# POWER_Management.net
KiCad netlist of a schematic drawn in Altium Designer
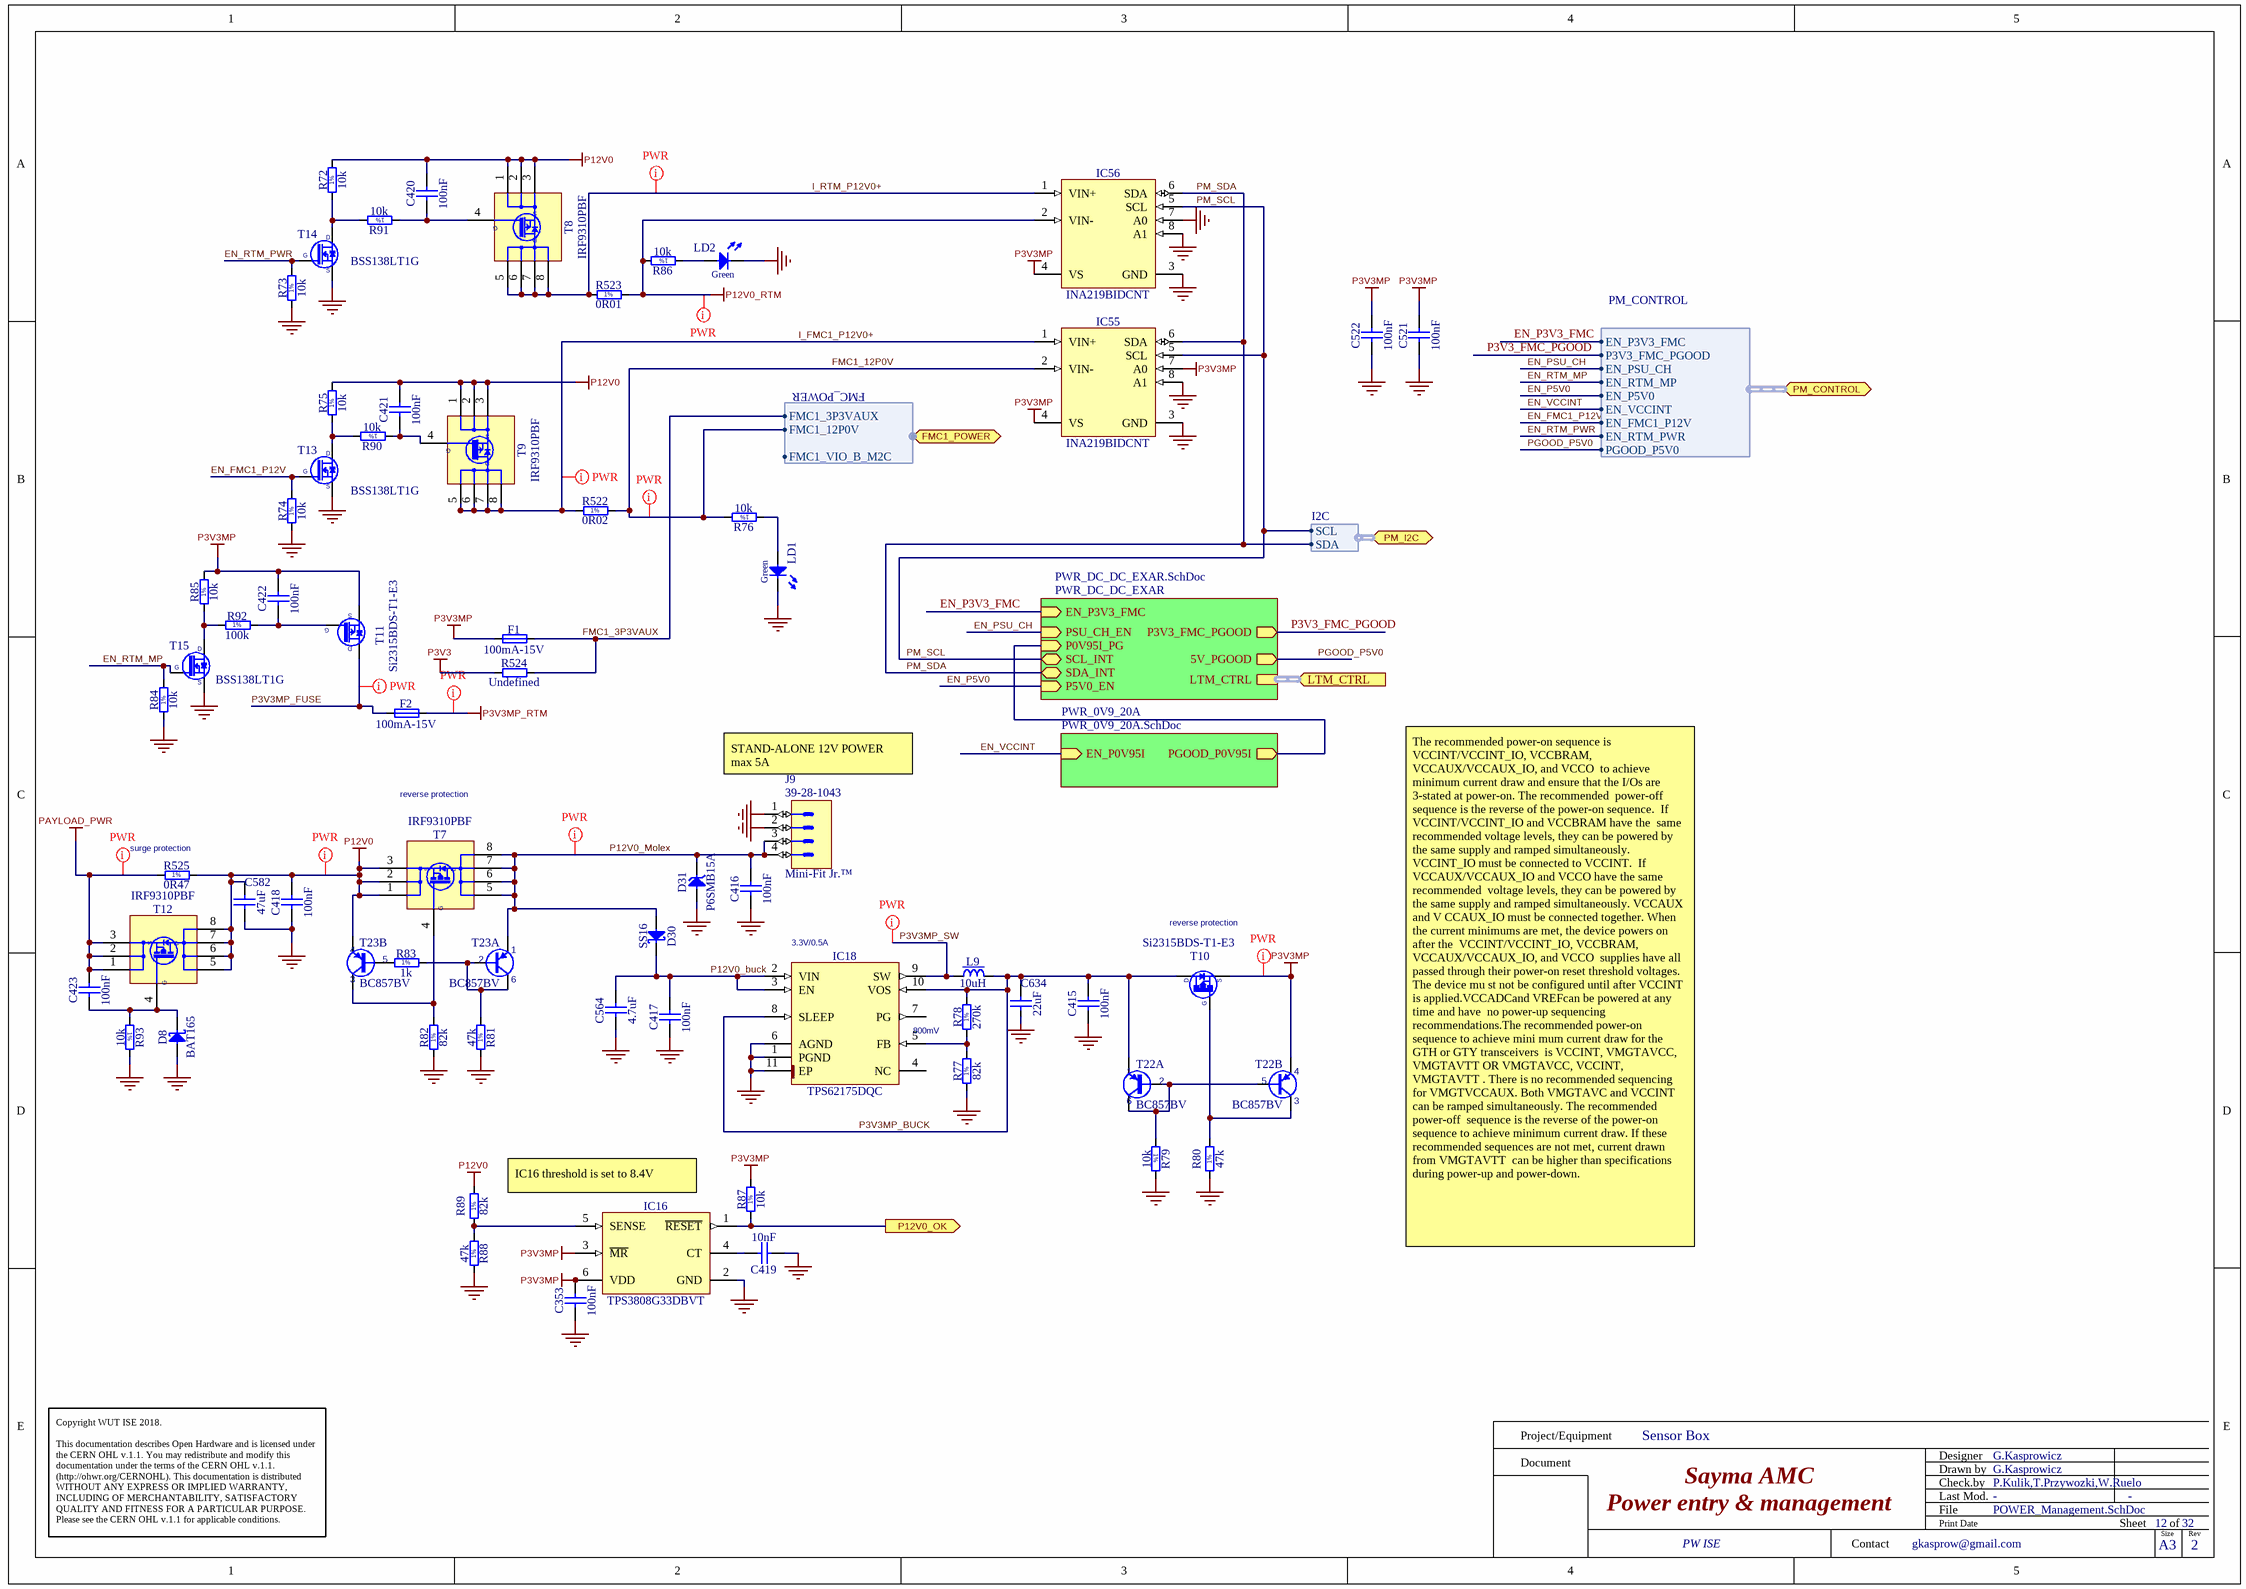
[diagram p0: POWER_Management.SchDoc]

(export (version "E")
  (design (tool "Eeschema 10.0.6"))
  (components
    (comp (ref "C353")
      (value "100nF")
      (footprint "CAPC1005X55N")
      (description "Non-polarised capacitor")
      (fields
        (field (name "MANUFACTURER PART NUMBER") "CC0402_100NF_16V_10%_X5R")
        (field (name "MANUFACTURER") "GENERIC")
        (field (name "AUTHOR") "CERN DEM JLC")
      )
      (libsource (lib "Capacitors") (part "Capacitor - non polarized"))
    )
    (comp (ref "C415")
      (value "100nF")
      (footprint "CAPC1005X55N")
      (description "Non-polarised capacitor")
      (fields
        (field (name "MANUFACTURER PART NUMBER") "CC0402_100NF_16V_10%_X5R")
        (field (name "MANUFACTURER") "GENERIC")
        (field (name "AUTHOR") "CERN DEM JLC")
      )
      (libsource (lib "Capacitors") (part "Capacitor - non polarized"))
    )
    (comp (ref "C416")
      (value "100nF")
      (footprint "CAPC1005X55N")
      (description "Non-polarised capacitor")
      (fields
        (field (name "MANUFACTURER PART NUMBER") "CC0402_100NF_16V_10%_X5R")
        (field (name "MANUFACTURER") "GENERIC")
        (field (name "AUTHOR") "CERN DEM JLC")
      )
      (libsource (lib "Capacitors") (part "Capacitor - non polarized"))
    )
    (comp (ref "C417")
      (value "100nF")
      (footprint "CAPC1005X55N")
      (description "Non-polarised capacitor")
      (fields
        (field (name "MANUFACTURER PART NUMBER") "CC0402_100NF_16V_10%_X5R")
        (field (name "MANUFACTURER") "GENERIC")
        (field (name "AUTHOR") "CERN DEM JLC")
      )
      (libsource (lib "Capacitors") (part "Capacitor - non polarized"))
    )
    (comp (ref "C418")
      (value "100nF")
      (footprint "CAPC1005X55N")
      (description "Non-polarised capacitor")
      (fields
        (field (name "MANUFACTURER PART NUMBER") "CC0402_100NF_16V_10%_X5R")
        (field (name "MANUFACTURER") "GENERIC")
        (field (name "AUTHOR") "CERN DEM JLC")
      )
      (libsource (lib "Capacitors") (part "Capacitor - non polarized"))
    )
    (comp (ref "C419")
      (value "10nF")
      (footprint "CAPC1005X55N")
      (description "Non-polarised capacitor")
      (fields
        (field (name "MANUFACTURER PART NUMBER") "CC0402_10NF_16V_10%_X7R")
        (field (name "MANUFACTURER") "GENERIC")
        (field (name "AUTHOR") "CERN DEM JLC")
      )
      (libsource (lib "Capacitors") (part "Capacitor - non polarized"))
    )
    (comp (ref "C420")
      (value "100nF")
      (footprint "CAPC1005X55N")
      (description "Non-polarised capacitor")
      (fields
        (field (name "MANUFACTURER PART NUMBER") "CC0402_100NF_16V_10%_X5R")
        (field (name "MANUFACTURER") "GENERIC")
        (field (name "AUTHOR") "CERN DEM JLC")
      )
      (libsource (lib "Capacitors") (part "Capacitor - non polarized"))
    )
    (comp (ref "C421")
      (value "100nF")
      (footprint "CAPC1005X55N")
      (description "Non-polarised capacitor")
      (fields
        (field (name "MANUFACTURER PART NUMBER") "CC0402_100NF_16V_10%_X5R")
        (field (name "MANUFACTURER") "GENERIC")
        (field (name "AUTHOR") "CERN DEM JLC")
      )
      (libsource (lib "Capacitors") (part "Capacitor - non polarized"))
    )
    (comp (ref "C422")
      (value "100nF")
      (footprint "CAPC1005X55N")
      (description "Non-polarised capacitor")
      (fields
        (field (name "MANUFACTURER PART NUMBER") "CC0402_100NF_16V_10%_X5R")
        (field (name "MANUFACTURER") "GENERIC")
        (field (name "AUTHOR") "CERN DEM JLC")
      )
      (libsource (lib "Capacitors") (part "Capacitor - non polarized"))
    )
    (comp (ref "C423")
      (value "100nF")
      (footprint "CAPC1005X55N")
      (description "Non-polarised capacitor")
      (fields
        (field (name "MANUFACTURER PART NUMBER") "CC0402_100NF_16V_10%_X5R")
        (field (name "MANUFACTURER") "GENERIC")
        (field (name "AUTHOR") "CERN DEM JLC")
      )
      (libsource (lib "Capacitors") (part "Capacitor - non polarized"))
    )
    (comp (ref "C521")
      (value "100nF")
      (footprint "CAPC1005X55N")
      (description "Non-polarised capacitor")
      (fields
        (field (name "MANUFACTURER PART NUMBER") "CC0402_100NF_16V_10%_X5R")
        (field (name "MANUFACTURER") "GENERIC")
        (field (name "AUTHOR") "CERN DEM JLC")
      )
      (libsource (lib "Capacitors") (part "Capacitor - non polarized"))
    )
    (comp (ref "C522")
      (value "100nF")
      (footprint "CAPC1005X55N")
      (description "Non-polarised capacitor")
      (fields
        (field (name "MANUFACTURER PART NUMBER") "CC0402_100NF_16V_10%_X5R")
        (field (name "MANUFACTURER") "GENERIC")
        (field (name "AUTHOR") "CERN DEM JLC")
      )
      (libsource (lib "Capacitors") (part "Capacitor - non polarized"))
    )
    (comp (ref "C564")
      (value "4.7uF")
      (footprint "CAPC1709X95N")
      (description "Non-polarised capacitor")
      (fields
        (field (name "MANUFACTURER PART NUMBER") "CC0603_4.7UF_16V_10%_X5R")
        (field (name "MANUFACTURER") "GENERIC")
        (field (name "AUTHOR") "CERN DEM JLC")
      )
      (libsource (lib "Capacitors") (part "Capacitor - non polarized"))
    )
    (comp (ref "C582")
      (value "47uF")
      (footprint "CAPC3216X180N")
      (description "Non-polarised capacitor")
      (fields
        (field (name "MANUFACTURER PART NUMBER") "CC1206_47UF_25V_20%_X5R")
        (field (name "MANUFACTURER") "GENERIC")
        (field (name "AUTHOR") "CERN DEM JLC")
      )
      (libsource (lib "Capacitors") (part "Capacitor - non polarized"))
    )
    (comp (ref "C634")
      (value "22uF")
      (footprint "CAPC2012X135N")
      (description "Non-polarised capacitor")
      (fields
        (field (name "MANUFACTURER PART NUMBER") "CC0805_22UF_16V_10%_X5R")
        (field (name "MANUFACTURER") "GENERIC")
        (field (name "AUTHOR") "CERN DEM JLC")
      )
      (libsource (lib "Capacitors") (part "Capacitor - non polarized"))
    )
    (comp (ref "D8")
      (value "BAT165")
      (footprint "SOD2512X110N")
      (description "Schottky Diode")
      (fields
        (field (name "MANUFACTURER") "INFINEON")
        (field (name "VOLTAGE") "40V")
        (field (name "AUTHOR") "CERN DEM JLC")
      )
      (libsource (lib "ICs And Semiconductors") (part "Diode Schottky"))
    )
    (comp (ref "D30")
      (value "SS16")
      (footprint "DIOM5127X229N")
      (description "Schottky Diode")
      (fields
        (field (name "MANUFACTURER") "VISHAY GENERAL SEMICONDUCTOR")
        (field (name "VOLTAGE") "60V")
        (field (name "AUTHOR") "CERN DEM JLC")
      )
      (libsource (lib "ICs And Semiconductors") (part "Diode Schottky"))
    )
    (comp (ref "D31")
      (value "P6SMB15A")
      (footprint "DIOM5436X261N")
      (description "Transient Voltage Suppressor Diode (Uni-Directional)")
      (fields
        (field (name "MANUFACTURER") "LITTELFUSE")
        (field (name "VOLTAGE") "15V")
        (field (name "AUTHOR") "CERN DEM JLC")
      )
      (libsource (lib "ICs And Semiconductors") (part "Diode TVS Uni-Directional"))
    )
    (comp (ref "F1")
      (value "100mA-15V")
      (footprint "FUSR_LITTELFUSE_0805L010")
      (description "Fuse")
      (fields
        (field (name "MANUFACTURER PART NUMBER") "0805L010YR")
        (field (name "MANUFACTURER") "LITTELFUSE")
        (field (name "AUTHOR") "CERN DEM JLC")
      )
      (libsource (lib "Eletro-mechanical") (part "Fuse"))
    )
    (comp (ref "F2")
      (value "100mA-15V")
      (footprint "FUSR_LITTELFUSE_0805L010")
      (description "Fuse")
      (fields
        (field (name "MANUFACTURER PART NUMBER") "0805L010YR")
        (field (name "MANUFACTURER") "LITTELFUSE")
        (field (name "AUTHOR") "CERN DEM JLC")
      )
      (libsource (lib "Eletro-mechanical") (part "Fuse"))
    )
    (comp (ref "IC16")
      (value "TPS3808G33DBVT")
      (footprint "SOT95P280X145-6N")
      (description "Low Quiescent Current, Programmable-Delay Supervisory Circuit")
      (fields (field (name "MANUFACTURER") "TEXAS INSTRUMENTS") (field (name "AUTHOR") "CERN DEM JLC"))
      (libsource (lib "ICs And Semiconductors") (part "TPS3808xxxDBV"))
    )
    (comp (ref "IC18")
      (value "TPS62175DQC")
      (footprint "SON50P200X300X80-11N-R94X250")
      (description "4.75-28VDC to 1-6VDC, 500mA Step-Down Converter With Sleep Mode")
      (fields (field (name "MANUFACTURER") "TEXAS INSTRUMENTS") (field (name "AUTHOR") "CERN DEM JMW"))
      (libsource (lib "ICs And Semiconductors") (part "TPS62175"))
    )
    (comp (ref "IC55")
      (value "INA219BIDCNT")
      (footprint "SOT65P280X145-8N")
      (description "Zero-Drift, Bi-Directional CURRENT/POWER MONITOR with I2C™ Interface")
      (fields (field (name "MANUFACTURER") "TEXAS INSTRUMENTS") (field (name "AUTHOR") "CERN DEM JLC"))
      (libsource (lib "ICs And Semiconductors") (part "INA219BIDCNT"))
    )
    (comp (ref "IC56")
      (value "INA219BIDCNT")
      (footprint "SOT65P280X145-8N")
      (description "Zero-Drift, Bi-Directional CURRENT/POWER MONITOR with I2C™ Interface")
      (fields (field (name "MANUFACTURER") "TEXAS INSTRUMENTS") (field (name "AUTHOR") "CERN DEM JLC"))
      (libsource (lib "ICs And Semiconductors") (part "INA219BIDCNT"))
    )
    (comp (ref "J9")
      (value "Mini-Fit Jr.™")
      (footprint "MOLEX_39-28-1043")
      (description "Connector 4 Male")
      (fields
        (field (name "MANUFACTURER PART NUMBER") "39-28-1043")
        (field (name "MANUFACTURER") "MOLEX")
        (field (name "PART NUMBER") "MOLEX_39-28-1043")
        (field (name "AUTHOR") "CERN DEM JLC")
      )
      (libsource (lib "Connectors") (part "Connector 4 Male"))
    )
    (comp (ref "L9")
      (value "10uH")
      (footprint "IND_MURATA-PS_8400")
      (description "Inductor With Core")
      (fields
        (field (name "MANUFACTURER PART NUMBER") "84103C")
        (field (name "MANUFACTURER") "MURATA POWER SOLUTIONS")
        (field (name "AUTHOR") "CERN DEM JLC")
      )
      (libsource (lib "Inductors & Transformers") (part "Inductor With Magnetic core"))
    )
    (comp (ref "LD1")
      (value "Green")
      (footprint "LED_KINGBRIGHT_KPH-1608CGCK")
      (description "LED Green 1C 2A")
      (fields
        (field (name "MANUFACTURER PART NUMBER") "KPH-1608CGCK")
        (field (name "MANUFACTURER") "KINGBRIGHT")
        (field (name "AUTHOR") "CERN DEM JLC")
      )
      (libsource (lib "ICs And Semiconductors") (part "LED Green 1C 2A"))
    )
    (comp (ref "LD2")
      (value "Green")
      (footprint "LED_KINGBRIGHT_KPH-1608CGCK")
      (description "LED Green 1C 2A")
      (fields
        (field (name "MANUFACTURER PART NUMBER") "KPH-1608CGCK")
        (field (name "MANUFACTURER") "KINGBRIGHT")
        (field (name "AUTHOR") "CERN DEM JLC")
      )
      (libsource (lib "ICs And Semiconductors") (part "LED Green 1C 2A"))
    )
    (comp (ref "R72")
      (value "10k")
      (footprint "RESC1005X40N")
      (description "Resistor - 1%")
      (fields
        (field (name "MANUFACTURER PART NUMBER") "R0402_10K_1%_0.0625W_100PPM")
        (field (name "MANUFACTURER") "GENERIC")
        (field (name "AUTHOR") "CERN DEM JLC")
      )
      (libsource (lib "Resistors") (part "Resistor - 1%"))
    )
    (comp (ref "R73")
      (value "10k")
      (footprint "RESC1005X40N")
      (description "Resistor - 1%")
      (fields
        (field (name "MANUFACTURER PART NUMBER") "R0402_10K_1%_0.0625W_100PPM")
        (field (name "MANUFACTURER") "GENERIC")
        (field (name "AUTHOR") "CERN DEM JLC")
      )
      (libsource (lib "Resistors") (part "Resistor - 1%"))
    )
    (comp (ref "R74")
      (value "10k")
      (footprint "RESC1005X40N")
      (description "Resistor - 1%")
      (fields
        (field (name "MANUFACTURER PART NUMBER") "R0402_10K_1%_0.0625W_100PPM")
        (field (name "MANUFACTURER") "GENERIC")
        (field (name "AUTHOR") "CERN DEM JLC")
      )
      (libsource (lib "Resistors") (part "Resistor - 1%"))
    )
    (comp (ref "R75")
      (value "10k")
      (footprint "RESC1005X40N")
      (description "Resistor - 1%")
      (fields
        (field (name "MANUFACTURER PART NUMBER") "R0402_10K_1%_0.0625W_100PPM")
        (field (name "MANUFACTURER") "GENERIC")
        (field (name "AUTHOR") "CERN DEM JLC")
      )
      (libsource (lib "Resistors") (part "Resistor - 1%"))
    )
    (comp (ref "R76")
      (value "10k")
      (footprint "RESC1005X40N")
      (description "Resistor - 1%")
      (fields
        (field (name "MANUFACTURER PART NUMBER") "R0402_10K_1%_0.0625W_100PPM")
        (field (name "MANUFACTURER") "GENERIC")
        (field (name "AUTHOR") "CERN DEM JLC")
      )
      (libsource (lib "Resistors") (part "Resistor - 1%"))
    )
    (comp (ref "R77")
      (value "82k")
      (footprint "RESC1005X40N")
      (description "Resistor - 1%")
      (fields
        (field (name "MANUFACTURER PART NUMBER") "R0402_82K_1%_0.0625W_100PPM")
        (field (name "MANUFACTURER") "GENERIC")
        (field (name "AUTHOR") "CERN DEM JLC")
      )
      (libsource (lib "Resistors") (part "Resistor - 1%"))
    )
    (comp (ref "R78")
      (value "270k")
      (footprint "RESC1005X40N")
      (description "Resistor - 1%")
      (fields
        (field (name "MANUFACTURER PART NUMBER") "R0402_270K_1%_0.0625W_100PPM")
        (field (name "MANUFACTURER") "GENERIC")
        (field (name "AUTHOR") "CERN DEM JLC")
      )
      (libsource (lib "Resistors") (part "Resistor - 1%"))
    )
    (comp (ref "R79")
      (value "10k")
      (footprint "RESC1005X40N")
      (description "Resistor - 1%")
      (fields
        (field (name "MANUFACTURER PART NUMBER") "R0402_10K_1%_0.0625W_100PPM")
        (field (name "MANUFACTURER") "GENERIC")
        (field (name "AUTHOR") "CERN DEM JLC")
      )
      (libsource (lib "Resistors") (part "Resistor - 1%"))
    )
    (comp (ref "R80")
      (value "47k")
      (footprint "RESC1005X40N")
      (description "Resistor - 1%")
      (fields
        (field (name "MANUFACTURER PART NUMBER") "R0402_47K_1%_0.0625W_100PPM")
        (field (name "MANUFACTURER") "GENERIC")
        (field (name "AUTHOR") "CERN DEM JLC")
      )
      (libsource (lib "Resistors") (part "Resistor - 1%"))
    )
    (comp (ref "R81")
      (value "47k")
      (footprint "RESC1005X40N")
      (description "Resistor - 1%")
      (fields
        (field (name "MANUFACTURER PART NUMBER") "R0402_47K_1%_0.0625W_100PPM")
        (field (name "MANUFACTURER") "GENERIC")
        (field (name "AUTHOR") "CERN DEM JLC")
      )
      (libsource (lib "Resistors") (part "Resistor - 1%"))
    )
    (comp (ref "R82")
      (value "82k")
      (footprint "RESC1005X40N")
      (description "Resistor - 1%")
      (fields
        (field (name "MANUFACTURER PART NUMBER") "R0402_82K_1%_0.0625W_100PPM")
        (field (name "MANUFACTURER") "GENERIC")
        (field (name "AUTHOR") "CERN DEM JLC")
      )
      (libsource (lib "Resistors") (part "Resistor - 1%"))
    )
    (comp (ref "R83")
      (value "1k")
      (footprint "RESC1005X40N")
      (description "Resistor - 1%")
      (fields
        (field (name "MANUFACTURER PART NUMBER") "R0402_1K_1%_0.0625W_100PPM")
        (field (name "MANUFACTURER") "GENERIC")
        (field (name "AUTHOR") "CERN DEM JLC")
      )
      (libsource (lib "Resistors") (part "Resistor - 1%"))
    )
    (comp (ref "R84")
      (value "10k")
      (footprint "RESC1005X40N")
      (description "Resistor - 1%")
      (fields
        (field (name "MANUFACTURER PART NUMBER") "R0402_10K_1%_0.0625W_100PPM")
        (field (name "MANUFACTURER") "GENERIC")
        (field (name "AUTHOR") "CERN DEM JLC")
      )
      (libsource (lib "Resistors") (part "Resistor - 1%"))
    )
    (comp (ref "R85")
      (value "10k")
      (footprint "RESC1005X40N")
      (description "Resistor - 1%")
      (fields
        (field (name "MANUFACTURER PART NUMBER") "R0402_10K_1%_0.0625W_100PPM")
        (field (name "MANUFACTURER") "GENERIC")
        (field (name "AUTHOR") "CERN DEM JLC")
      )
      (libsource (lib "Resistors") (part "Resistor - 1%"))
    )
    (comp (ref "R86")
      (value "10k")
      (footprint "RESC1005X40N")
      (description "Resistor - 1%")
      (fields
        (field (name "MANUFACTURER PART NUMBER") "R0402_10K_1%_0.0625W_100PPM")
        (field (name "MANUFACTURER") "GENERIC")
        (field (name "AUTHOR") "CERN DEM JLC")
      )
      (libsource (lib "Resistors") (part "Resistor - 1%"))
    )
    (comp (ref "R87")
      (value "10k")
      (footprint "RESC1005X40N")
      (description "Resistor - 1%")
      (fields
        (field (name "MANUFACTURER PART NUMBER") "R0402_10K_1%_0.0625W_100PPM")
        (field (name "MANUFACTURER") "GENERIC")
        (field (name "AUTHOR") "CERN DEM JLC")
      )
      (libsource (lib "Resistors") (part "Resistor - 1%"))
    )
    (comp (ref "R88")
      (value "47k")
      (footprint "RESC1005X40N")
      (description "Resistor - 1%")
      (fields
        (field (name "MANUFACTURER PART NUMBER") "R0402_47K_1%_0.0625W_100PPM")
        (field (name "MANUFACTURER") "GENERIC")
        (field (name "AUTHOR") "CERN DEM JLC")
      )
      (libsource (lib "Resistors") (part "Resistor - 1%"))
    )
    (comp (ref "R89")
      (value "82k")
      (footprint "RESC1005X40N")
      (description "Resistor - 1%")
      (fields
        (field (name "MANUFACTURER PART NUMBER") "R0402_82K_1%_0.0625W_100PPM")
        (field (name "MANUFACTURER") "GENERIC")
        (field (name "AUTHOR") "CERN DEM JLC")
      )
      (libsource (lib "Resistors") (part "Resistor - 1%"))
    )
    (comp (ref "R90")
      (value "10k")
      (footprint "RESC1005X40N")
      (description "Resistor - 1%")
      (fields
        (field (name "MANUFACTURER PART NUMBER") "R0402_10K_1%_0.0625W_100PPM")
        (field (name "MANUFACTURER") "GENERIC")
        (field (name "AUTHOR") "CERN DEM JLC")
      )
      (libsource (lib "Resistors") (part "Resistor - 1%"))
    )
    (comp (ref "R91")
      (value "10k")
      (footprint "RESC1005X40N")
      (description "Resistor - 1%")
      (fields
        (field (name "MANUFACTURER PART NUMBER") "R0402_10K_1%_0.0625W_100PPM")
        (field (name "MANUFACTURER") "GENERIC")
        (field (name "AUTHOR") "CERN DEM JLC")
      )
      (libsource (lib "Resistors") (part "Resistor - 1%"))
    )
    (comp (ref "R92")
      (value "100k")
      (footprint "RESC1005X40N")
      (description "Resistor - 1%")
      (fields
        (field (name "MANUFACTURER PART NUMBER") "R0402_100K_1%_0.0625W_100PPM")
        (field (name "MANUFACTURER") "GENERIC")
        (field (name "AUTHOR") "CERN DEM JLC")
      )
      (libsource (lib "Resistors") (part "Resistor - 1%"))
    )
    (comp (ref "R93")
      (value "10k")
      (footprint "RESC1005X40N")
      (description "Resistor - 1%")
      (fields
        (field (name "MANUFACTURER PART NUMBER") "R0402_10K_1%_0.0625W_100PPM")
        (field (name "MANUFACTURER") "GENERIC")
        (field (name "AUTHOR") "CERN DEM JLC")
      )
      (libsource (lib "Resistors") (part "Resistor - 1%"))
    )
    (comp (ref "R522")
      (value "0R02")
      (footprint "RESC_VISHAY_WSL2512_0R007-0R5")
      (description "Resistor - 1%")
      (fields
        (field (name "MANUFACTURER PART NUMBER") "WSL2512R0200FEA")
        (field (name "MANUFACTURER") "VISHAY DALE")
        (field (name "AUTHOR") "CERN DEM JLC")
      )
      (libsource (lib "Resistors") (part "Resistor - 1%"))
    )
    (comp (ref "R523")
      (value "0R01")
      (footprint "RESC_VISHAY_WSL2512_0R007-0R5")
      (description "Resistor - 1%")
      (fields
        (field (name "MANUFACTURER PART NUMBER") "WSL2512R0100FEA")
        (field (name "MANUFACTURER") "VISHAY DALE")
        (field (name "AUTHOR") "CERN DEM JLC")
      )
      (libsource (lib "Resistors") (part "Resistor - 1%"))
    )
    (comp (ref "R524")
      (value "Undefined")
      (footprint "RESC2012X60N")
      (description "Resistor")
      (fields
        (field (name "MANUFACTURER PART NUMBER") "R0805_NO-VALUE")
        (field (name "AUTHOR") "CERN DEM JLC")
      )
      (libsource (lib "Resistors") (part "Resistor"))
    )
    (comp (ref "R525")
      (value "0R47")
      (footprint "RESC3216X65N")
      (description "Resistor - 1%")
      (fields
        (field (name "MANUFACTURER PART NUMBER") "RL1206FR-7W0R47  (35051914707)")
        (field (name "MANUFACTURER") "YAGEO PHYCOMP")
        (field (name "AUTHOR") "CERN DEM JLC")
      )
      (libsource (lib "Resistors") (part "Resistor - 1%"))
    )
    (comp (ref "T7")
      (value "IRF9310PBF")
      (footprint "SOIC127P600X175-8N")
      (description "-30V -20A P-Channel HEXFET® Power MOSFET")
      (fields (field (name "MANUFACTURER") "INTERNATIONAL RECTIFIER") (field (name "AUTHOR") "CERN DEM JLC"))
      (libsource (lib "ICs And Semiconductors") (part "IRF9310"))
    )
    (comp (ref "T8")
      (value "IRF9310PBF")
      (footprint "SOIC127P600X175-8N")
      (description "-30V -20A P-Channel HEXFET® Power MOSFET")
      (fields (field (name "MANUFACTURER") "INTERNATIONAL RECTIFIER") (field (name "AUTHOR") "CERN DEM JLC"))
      (libsource (lib "") (part "IRF9310_1"))
    )
    (comp (ref "T9")
      (value "IRF9310PBF")
      (footprint "SOIC127P600X175-8N")
      (description "-30V -20A P-Channel HEXFET® Power MOSFET")
      (fields (field (name "MANUFACTURER") "INTERNATIONAL RECTIFIER") (field (name "AUTHOR") "CERN DEM JLC"))
      (libsource (lib "") (part "IRF9310_1"))
    )
    (comp (ref "T10")
      (value "Si2315BDS-T1-E3")
      (footprint "SOT95P237X112-3N")
      (description "P-CHANNEL MOSFET WITH DIODE")
      (fields (field (name "MANUFACTURER") "VISHAY SILICONIX") (field (name "AUTHOR") "CERN DEM JLC"))
      (libsource (lib "ICs And Semiconductors") (part "P-MOSFET-D 1G 2S 3D"))
    )
    (comp (ref "T11")
      (value "Si2315BDS-T1-E3")
      (footprint "SOT95P237X112-3N")
      (description "P-CHANNEL MOSFET WITH DIODE")
      (fields (field (name "MANUFACTURER") "VISHAY SILICONIX") (field (name "AUTHOR") "CERN DEM JLC"))
      (libsource (lib "ICs And Semiconductors") (part "P-MOSFET-D 1G 2S 3D"))
    )
    (comp (ref "T12")
      (value "IRF9310PBF")
      (footprint "SOIC127P600X175-8N")
      (description "-30V -20A P-Channel HEXFET® Power MOSFET")
      (fields (field (name "MANUFACTURER") "INTERNATIONAL RECTIFIER") (field (name "AUTHOR") "CERN DEM JLC"))
      (libsource (lib "ICs And Semiconductors") (part "IRF9310"))
    )
    (comp (ref "T13")
      (value "BSS138LT1G")
      (footprint "SOT95P240X110-3N")
      (description "N-CHANNEL MOSFET WITH DIODE")
      (fields (field (name "MANUFACTURER") "ON SEMICONDUCTOR") (field (name "AUTHOR") "CERN DEM JLC"))
      (libsource (lib "ICs And Semiconductors") (part "N-MOSFET-D 1G 2S 3D"))
    )
    (comp (ref "T14")
      (value "BSS138LT1G")
      (footprint "SOT95P240X110-3N")
      (description "N-CHANNEL MOSFET WITH DIODE")
      (fields (field (name "MANUFACTURER") "ON SEMICONDUCTOR") (field (name "AUTHOR") "CERN DEM JLC"))
      (libsource (lib "ICs And Semiconductors") (part "N-MOSFET-D 1G 2S 3D"))
    )
    (comp (ref "T15")
      (value "BSS138LT1G")
      (footprint "SOT95P240X110-3N")
      (description "N-CHANNEL MOSFET WITH DIODE")
      (fields (field (name "MANUFACTURER") "ON SEMICONDUCTOR") (field (name "AUTHOR") "CERN DEM JLC"))
      (libsource (lib "ICs And Semiconductors") (part "N-MOSFET-D 1G 2S 3D"))
    )
    (comp (ref "T22")
      (value "BC857BV")
      (footprint "SOTFL50P160X60-6N")
      (description "45V, 100mA PNP General Purpose Double Transistor")
      (fields (field (name "MANUFACTURER") "NXP SEMICONDUCTORS") (field (name "AUTHOR") "CERN DEM JLC"))
      (libsource (lib "ICs And Semiconductors") (part "BC857BV"))
    )
    (comp (ref "T23")
      (value "BC857BV")
      (footprint "SOTFL50P160X60-6N")
      (description "45V, 100mA PNP General Purpose Double Transistor")
      (fields (field (name "MANUFACTURER") "NXP SEMICONDUCTORS") (field (name "AUTHOR") "CERN DEM JLC"))
      (libsource (lib "") (part "BC857BV_1"))
    )
  )
  (nets
    (net (code "5") (name "/EN_FMC1_P12V") (class "Default")
      (node (ref "R74") (pin "2") (pinfunction "2_2") (pintype "passive"))
      (node (ref "T13") (pin "1") (pinfunction "G_1") (pintype "passive"))
    )
    (net (code "9") (name "/EN_RTM_MP") (class "Default")
      (node (ref "R84") (pin "2") (pinfunction "2_2") (pintype "passive"))
      (node (ref "T15") (pin "1") (pinfunction "G_1") (pintype "passive"))
    )
    (net (code "10") (name "/EN_RTM_PWR") (class "Default")
      (node (ref "R73") (pin "2") (pinfunction "2_2") (pintype "passive"))
      (node (ref "T14") (pin "1") (pinfunction "G_1") (pintype "passive"))
    )
    (net (code "12") (name "/FMC1_3P3VAUX") (class "Default")
      (node (ref "F1") (pin "2") (pinfunction "2_2") (pintype "passive"))
      (node (ref "R524") (pin "2") (pinfunction "2_2") (pintype "passive"))
    )
    (net (code "13") (name "/FMC1_12P0V") (class "Default")
      (node (ref "IC55") (pin "2") (pinfunction "VIN-_2") (pintype "input"))
      (node (ref "R522") (pin "2") (pinfunction "2_2") (pintype "passive"))
      (node (ref "R76") (pin "2") (pinfunction "2_2") (pintype "passive"))
    )
    (net (code "14") (name "/I_FMC1_P12V0+") (class "Default")
      (node (ref "IC55") (pin "1") (pinfunction "VIN+_1") (pintype "input"))
      (node (ref "R522") (pin "1") (pinfunction "1_1") (pintype "passive"))
      (node (ref "T9") (pin "5") (pinfunction "D_5") (pintype "passive"))
      (node (ref "T9") (pin "6") (pinfunction "D_6") (pintype "passive"))
      (node (ref "T9") (pin "7") (pinfunction "D_7") (pintype "passive"))
      (node (ref "T9") (pin "8") (pinfunction "D_8") (pintype "passive"))
    )
    (net (code "15") (name "/I_RTM_P12V0+") (class "Default")
      (node (ref "IC56") (pin "1") (pinfunction "VIN+_1") (pintype "input"))
      (node (ref "R523") (pin "1") (pinfunction "1_1") (pintype "passive"))
      (node (ref "T8") (pin "5") (pinfunction "D_5") (pintype "passive"))
      (node (ref "T8") (pin "6") (pinfunction "D_6") (pintype "passive"))
      (node (ref "T8") (pin "7") (pinfunction "D_7") (pintype "passive"))
      (node (ref "T8") (pin "8") (pinfunction "D_8") (pintype "passive"))
    )
    (net (code "17") (name "/P3V3MP_BUCK") (class "Default")
      (node (ref "C415") (pin "2") (pinfunction "2_2") (pintype "passive"))
      (node (ref "C634") (pin "2") (pinfunction "2_2") (pintype "passive"))
      (node (ref "IC18") (pin "10") (pinfunction "VOS_10") (pintype "input"))
      (node (ref "IC18") (pin "8") (pinfunction "SLEEP_8") (pintype "input"))
      (node (ref "L9") (pin "2") (pinfunction "2_2") (pintype "passive"))
      (node (ref "R78") (pin "2") (pinfunction "2_2") (pintype "passive"))
      (node (ref "T10") (pin "3") (pinfunction "D_3") (pintype "passive"))
      (node (ref "T22") (pin "1") (pinfunction "E_1") (pintype "passive"))
    )
    (net (code "18") (name "/P3V3MP_FUSE") (class "Default")
      (node (ref "F2") (pin "1") (pinfunction "1_1") (pintype "passive"))
      (node (ref "T11") (pin "3") (pinfunction "D_3") (pintype "passive"))
    )
    (net (code "19") (name "/P3V3MP_SW") (class "Default")
      (node (ref "IC18") (pin "9") (pinfunction "SW_9") (pintype "output"))
      (node (ref "L9") (pin "1") (pinfunction "1_1") (pintype "passive"))
    )
    (net (code "21") (name "/P12V0_Molex") (class "Default")
      (node (ref "C416") (pin "2") (pinfunction "2_2") (pintype "passive"))
      (node (ref "D30") (pin "2") (pinfunction "A_2") (pintype "passive"))
      (node (ref "D31") (pin "1") (pinfunction "C_1") (pintype "passive"))
      (node (ref "J9") (pin "3") (pinfunction "3_3") (pintype "bidirectional"))
      (node (ref "J9") (pin "4") (pinfunction "4_4") (pintype "bidirectional"))
      (node (ref "T23") (pin "1") (pinfunction "E_1") (pintype "passive"))
      (node (ref "T7") (pin "5") (pinfunction "D_5") (pintype "passive"))
      (node (ref "T7") (pin "6") (pinfunction "D_6") (pintype "passive"))
      (node (ref "T7") (pin "7") (pinfunction "D_7") (pintype "passive"))
      (node (ref "T7") (pin "8") (pinfunction "D_8") (pintype "passive"))
    )
    (net (code "22") (name "/P12V0_OK") (class "Default")
      (node (ref "IC16") (pin "1") (pinfunction "~{RESET}_1") (pintype "output"))
      (node (ref "R87") (pin "1") (pinfunction "1_1") (pintype "passive"))
    )
    (net (code "23") (name "/P12V0_buck") (class "Default")
      (node (ref "C417") (pin "2") (pinfunction "2_2") (pintype "passive"))
      (node (ref "C564") (pin "2") (pinfunction "2_2") (pintype "passive"))
      (node (ref "D30") (pin "1") (pinfunction "C_1") (pintype "passive"))
      (node (ref "IC18") (pin "2") (pinfunction "VIN_2") (pintype "input"))
      (node (ref "IC18") (pin "3") (pinfunction "EN_3") (pintype "input"))
    )
    (net (code "26") (name "/PM_SCL") (class "Default")
      (node (ref "IC55") (pin "5") (pinfunction "SCL_5") (pintype "input"))
      (node (ref "IC56") (pin "5") (pinfunction "SCL_5") (pintype "input"))
    )
    (net (code "27") (name "/PM_SDA") (class "Default")
      (node (ref "IC55") (pin "6") (pinfunction "SDA_6") (pintype "bidirectional"))
      (node (ref "IC56") (pin "6") (pinfunction "SDA_6") (pintype "bidirectional"))
    )
    (net (code "31") (name "GND") (class "Default")
      (node (ref "C353") (pin "1") (pinfunction "1_1") (pintype "passive"))
      (node (ref "C415") (pin "1") (pinfunction "1_1") (pintype "passive"))
      (node (ref "C416") (pin "1") (pinfunction "1_1") (pintype "passive"))
      (node (ref "C417") (pin "1") (pinfunction "1_1") (pintype "passive"))
      (node (ref "C418") (pin "1") (pinfunction "1_1") (pintype "passive"))
      (node (ref "C419") (pin "1") (pinfunction "1_1") (pintype "passive"))
      (node (ref "C521") (pin "1") (pinfunction "1_1") (pintype "passive"))
      (node (ref "C522") (pin "1") (pinfunction "1_1") (pintype "passive"))
      (node (ref "C564") (pin "1") (pinfunction "1_1") (pintype "passive"))
      (node (ref "C582") (pin "1") (pinfunction "1_1") (pintype "passive"))
      (node (ref "C634") (pin "1") (pinfunction "1_1") (pintype "passive"))
      (node (ref "D31") (pin "2") (pinfunction "A_2") (pintype "passive"))
      (node (ref "D8") (pin "2") (pinfunction "A_2") (pintype "passive"))
      (node (ref "IC16") (pin "2") (pinfunction "GND_2") (pintype "power_in"))
      (node (ref "IC18") (pin "1") (pinfunction "PGND_1") (pintype "power_in"))
      (node (ref "IC18") (pin "11") (pinfunction "EP_11") (pintype "power_in"))
      (node (ref "IC18") (pin "6") (pinfunction "AGND_6") (pintype "power_in"))
      (node (ref "IC55") (pin "3") (pinfunction "GND_3") (pintype "power_in"))
      (node (ref "IC55") (pin "8") (pinfunction "A1_8") (pintype "input"))
      (node (ref "IC56") (pin "3") (pinfunction "GND_3") (pintype "power_in"))
      (node (ref "IC56") (pin "7") (pinfunction "A0_7") (pintype "input"))
      (node (ref "IC56") (pin "8") (pinfunction "A1_8") (pintype "input"))
      (node (ref "J9") (pin "1") (pinfunction "1_1") (pintype "bidirectional"))
      (node (ref "J9") (pin "2") (pinfunction "2_2") (pintype "bidirectional"))
      (node (ref "LD1") (pin "1") (pinfunction "C_1") (pintype "passive"))
      (node (ref "LD2") (pin "1") (pinfunction "C_1") (pintype "passive"))
      (node (ref "R73") (pin "1") (pinfunction "1_1") (pintype "passive"))
      (node (ref "R74") (pin "1") (pinfunction "1_1") (pintype "passive"))
      (node (ref "R77") (pin "1") (pinfunction "1_1") (pintype "passive"))
      (node (ref "R79") (pin "2") (pinfunction "2_2") (pintype "passive"))
      (node (ref "R80") (pin "1") (pinfunction "1_1") (pintype "passive"))
      (node (ref "R81") (pin "1") (pinfunction "1_1") (pintype "passive"))
      (node (ref "R82") (pin "1") (pinfunction "1_1") (pintype "passive"))
      (node (ref "R84") (pin "1") (pinfunction "1_1") (pintype "passive"))
      (node (ref "R88") (pin "1") (pinfunction "1_1") (pintype "passive"))
      (node (ref "R93") (pin "2") (pinfunction "2_2") (pintype "passive"))
      (node (ref "T13") (pin "2") (pinfunction "S_2") (pintype "passive"))
      (node (ref "T14") (pin "2") (pinfunction "S_2") (pintype "passive"))
      (node (ref "T15") (pin "2") (pinfunction "S_2") (pintype "passive"))
    )
    (net (code "32") (name "Net-(C420-Pad1)") (class "Default")
      (node (ref "C420") (pin "1") (pinfunction "1_1") (pintype "passive"))
      (node (ref "R91") (pin "1") (pinfunction "1_1") (pintype "passive"))
      (node (ref "T8") (pin "4") (pinfunction "S_4") (pintype "passive"))
    )
    (net (code "33") (name "Net-(C421-Pad1)") (class "Default")
      (node (ref "C421") (pin "1") (pinfunction "1_1") (pintype "passive"))
      (node (ref "R90") (pin "1") (pinfunction "1_1") (pintype "passive"))
      (node (ref "T9") (pin "4") (pinfunction "S_4") (pintype "passive"))
    )
    (net (code "34") (name "Net-(D8-C)") (class "Default")
      (node (ref "C423") (pin "1") (pinfunction "1_1") (pintype "passive"))
      (node (ref "D8") (pin "1") (pinfunction "C_1") (pintype "passive"))
      (node (ref "R93") (pin "1") (pinfunction "1_1") (pintype "passive"))
      (node (ref "T12") (pin "4") (pinfunction "S_4") (pintype "passive"))
    )
    (net (code "35") (name "Net-(IC16-CT)") (class "Default")
      (node (ref "C419") (pin "2") (pinfunction "2_2") (pintype "passive"))
      (node (ref "IC16") (pin "4") (pinfunction "CT_4") (pintype "passive"))
    )
    (net (code "36") (name "Net-(IC16-SENSE)") (class "Default")
      (node (ref "IC16") (pin "5") (pinfunction "SENSE_5") (pintype "input"))
      (node (ref "R88") (pin "2") (pinfunction "2_2") (pintype "passive"))
      (node (ref "R89") (pin "1") (pinfunction "1_1") (pintype "passive"))
    )
    (net (code "37") (name "Net-(IC18-FB)") (class "Default")
      (node (ref "IC18") (pin "5") (pinfunction "FB_5") (pintype "input"))
      (node (ref "R77") (pin "2") (pinfunction "2_2") (pintype "passive"))
      (node (ref "R78") (pin "1") (pinfunction "1_1") (pintype "passive"))
    )
    (net (code "38") (name "Net-(LD1-A)") (class "Default")
      (node (ref "LD1") (pin "2") (pinfunction "A_2") (pintype "passive"))
      (node (ref "R76") (pin "1") (pinfunction "1_1") (pintype "passive"))
    )
    (net (code "39") (name "Net-(LD2-A)") (class "Default")
      (node (ref "LD2") (pin "2") (pinfunction "A_2") (pintype "passive"))
      (node (ref "R86") (pin "1") (pinfunction "1_1") (pintype "passive"))
    )
    (net (code "40") (name "Net-(T10-G)") (class "Default")
      (node (ref "R80") (pin "2") (pinfunction "2_2") (pintype "passive"))
      (node (ref "T10") (pin "1") (pinfunction "G_1") (pintype "passive"))
      (node (ref "T22") (pin "3") (pinfunction "C_3") (pintype "passive"))
    )
    (net (code "41") (name "Net-(T11-G)") (class "Default")
      (node (ref "C422") (pin "1") (pinfunction "1_1") (pintype "passive"))
      (node (ref "R92") (pin "1") (pinfunction "1_1") (pintype "passive"))
      (node (ref "T11") (pin "1") (pinfunction "G_1") (pintype "passive"))
    )
    (net (code "42") (name "Net-(T13-D)") (class "Default")
      (node (ref "R75") (pin "1") (pinfunction "1_1") (pintype "passive"))
      (node (ref "R90") (pin "2") (pinfunction "2_2") (pintype "passive"))
      (node (ref "T13") (pin "3") (pinfunction "D_3") (pintype "passive"))
    )
    (net (code "43") (name "Net-(T14-D)") (class "Default")
      (node (ref "R72") (pin "1") (pinfunction "1_1") (pintype "passive"))
      (node (ref "R91") (pin "2") (pinfunction "2_2") (pintype "passive"))
      (node (ref "T14") (pin "3") (pinfunction "D_3") (pintype "passive"))
    )
    (net (code "44") (name "Net-(T15-D)") (class "Default")
      (node (ref "R85") (pin "1") (pinfunction "1_1") (pintype "passive"))
      (node (ref "R92") (pin "2") (pinfunction "2_2") (pintype "passive"))
      (node (ref "T15") (pin "3") (pinfunction "D_3") (pintype "passive"))
    )
    (net (code "45") (name "Net-(T22A-B)") (class "Default")
      (node (ref "R79") (pin "1") (pinfunction "1_1") (pintype "passive"))
      (node (ref "T22") (pin "2") (pinfunction "B_2") (pintype "passive"))
      (node (ref "T22") (pin "5") (pinfunction "B_5") (pintype "passive"))
      (node (ref "T22") (pin "6") (pinfunction "C_6") (pintype "passive"))
    )
    (net (code "46") (name "Net-(T23A-B)") (class "Default")
      (node (ref "R81") (pin "2") (pinfunction "2_2") (pintype "passive"))
      (node (ref "R83") (pin "2") (pinfunction "2_2") (pintype "passive"))
      (node (ref "T23") (pin "2") (pinfunction "B_2") (pintype "passive"))
      (node (ref "T23") (pin "6") (pinfunction "C_6") (pintype "passive"))
    )
    (net (code "47") (name "Net-(T23B-B)") (class "Default")
      (node (ref "R83") (pin "1") (pinfunction "1_1") (pintype "passive"))
      (node (ref "T23") (pin "5") (pinfunction "B_5") (pintype "passive"))
    )
    (net (code "48") (name "Net-(T23B-C)") (class "Default")
      (node (ref "R82") (pin "2") (pinfunction "2_2") (pintype "passive"))
      (node (ref "T23") (pin "3") (pinfunction "C_3") (pintype "passive"))
      (node (ref "T7") (pin "4") (pinfunction "S_4") (pintype "passive"))
    )
    (net (code "49") (name "P3V3") (class "Default")
      (node (ref "R524") (pin "1") (pinfunction "1_1") (pintype "passive"))
    )
    (net (code "50") (name "P3V3MP") (class "Default")
      (node (ref "C353") (pin "2") (pinfunction "2_2") (pintype "passive"))
      (node (ref "C422") (pin "2") (pinfunction "2_2") (pintype "passive"))
      (node (ref "C521") (pin "2") (pinfunction "2_2") (pintype "passive"))
      (node (ref "C522") (pin "2") (pinfunction "2_2") (pintype "passive"))
      (node (ref "F1") (pin "1") (pinfunction "1_1") (pintype "passive"))
      (node (ref "IC16") (pin "3") (pinfunction "~{MR}_3") (pintype "input"))
      (node (ref "IC16") (pin "6") (pinfunction "VDD_6") (pintype "power_in"))
      (node (ref "IC55") (pin "4") (pinfunction "VS_4") (pintype "power_in"))
      (node (ref "IC55") (pin "7") (pinfunction "A0_7") (pintype "input"))
      (node (ref "IC56") (pin "4") (pinfunction "VS_4") (pintype "power_in"))
      (node (ref "R85") (pin "2") (pinfunction "2_2") (pintype "passive"))
      (node (ref "R87") (pin "2") (pinfunction "2_2") (pintype "passive"))
      (node (ref "T10") (pin "2") (pinfunction "S_2") (pintype "passive"))
      (node (ref "T11") (pin "2") (pinfunction "S_2") (pintype "passive"))
      (node (ref "T22") (pin "4") (pinfunction "E_4") (pintype "passive"))
    )
    (net (code "51") (name "P3V3MP_RTM") (class "Default")
      (node (ref "F2") (pin "2") (pinfunction "2_2") (pintype "passive"))
    )
    (net (code "52") (name "P12V0") (class "Default")
      (node (ref "C418") (pin "2") (pinfunction "2_2") (pintype "passive"))
      (node (ref "C420") (pin "2") (pinfunction "2_2") (pintype "passive"))
      (node (ref "C421") (pin "2") (pinfunction "2_2") (pintype "passive"))
      (node (ref "C582") (pin "2") (pinfunction "2_2") (pintype "passive"))
      (node (ref "R525") (pin "2") (pinfunction "2_2") (pintype "passive"))
      (node (ref "R72") (pin "2") (pinfunction "2_2") (pintype "passive"))
      (node (ref "R75") (pin "2") (pinfunction "2_2") (pintype "passive"))
      (node (ref "R89") (pin "2") (pinfunction "2_2") (pintype "passive"))
      (node (ref "T12") (pin "5") (pinfunction "D_5") (pintype "passive"))
      (node (ref "T12") (pin "6") (pinfunction "D_6") (pintype "passive"))
      (node (ref "T12") (pin "7") (pinfunction "D_7") (pintype "passive"))
      (node (ref "T12") (pin "8") (pinfunction "D_8") (pintype "passive"))
      (node (ref "T23") (pin "4") (pinfunction "E_4") (pintype "passive"))
      (node (ref "T7") (pin "1") (pinfunction "S_1") (pintype "passive"))
      (node (ref "T7") (pin "2") (pinfunction "S_2") (pintype "passive"))
      (node (ref "T7") (pin "3") (pinfunction "S_3") (pintype "passive"))
      (node (ref "T8") (pin "1") (pinfunction "S_1") (pintype "passive"))
      (node (ref "T8") (pin "2") (pinfunction "S_2") (pintype "passive"))
      (node (ref "T8") (pin "3") (pinfunction "S_3") (pintype "passive"))
      (node (ref "T9") (pin "1") (pinfunction "S_1") (pintype "passive"))
      (node (ref "T9") (pin "2") (pinfunction "S_2") (pintype "passive"))
      (node (ref "T9") (pin "3") (pinfunction "S_3") (pintype "passive"))
    )
    (net (code "53") (name "P12V0_RTM") (class "Default")
      (node (ref "IC56") (pin "2") (pinfunction "VIN-_2") (pintype "input"))
      (node (ref "R523") (pin "2") (pinfunction "2_2") (pintype "passive"))
      (node (ref "R86") (pin "2") (pinfunction "2_2") (pintype "passive"))
    )
    (net (code "54") (name "PAYLOAD_PWR") (class "Default")
      (node (ref "C423") (pin "2") (pinfunction "2_2") (pintype "passive"))
      (node (ref "R525") (pin "1") (pinfunction "1_1") (pintype "passive"))
      (node (ref "T12") (pin "1") (pinfunction "S_1") (pintype "passive"))
      (node (ref "T12") (pin "2") (pinfunction "S_2") (pintype "passive"))
      (node (ref "T12") (pin "3") (pinfunction "S_3") (pintype "passive"))
    )
    (net (code "55") (name "unconnected-(IC18-NC-Pad4)") (class "Default")
      (node (ref "IC18") (pin "4") (pinfunction "NC_4") (pintype "passive"))
    )
    (net (code "56") (name "unconnected-(IC18-PG-Pad7)") (class "Default")
      (node (ref "IC18") (pin "7") (pinfunction "PG_7") (pintype "output"))
    )
  )
)
